# Comm_Interface.net
KiCad netlist of a schematic drawn in Altium Designer
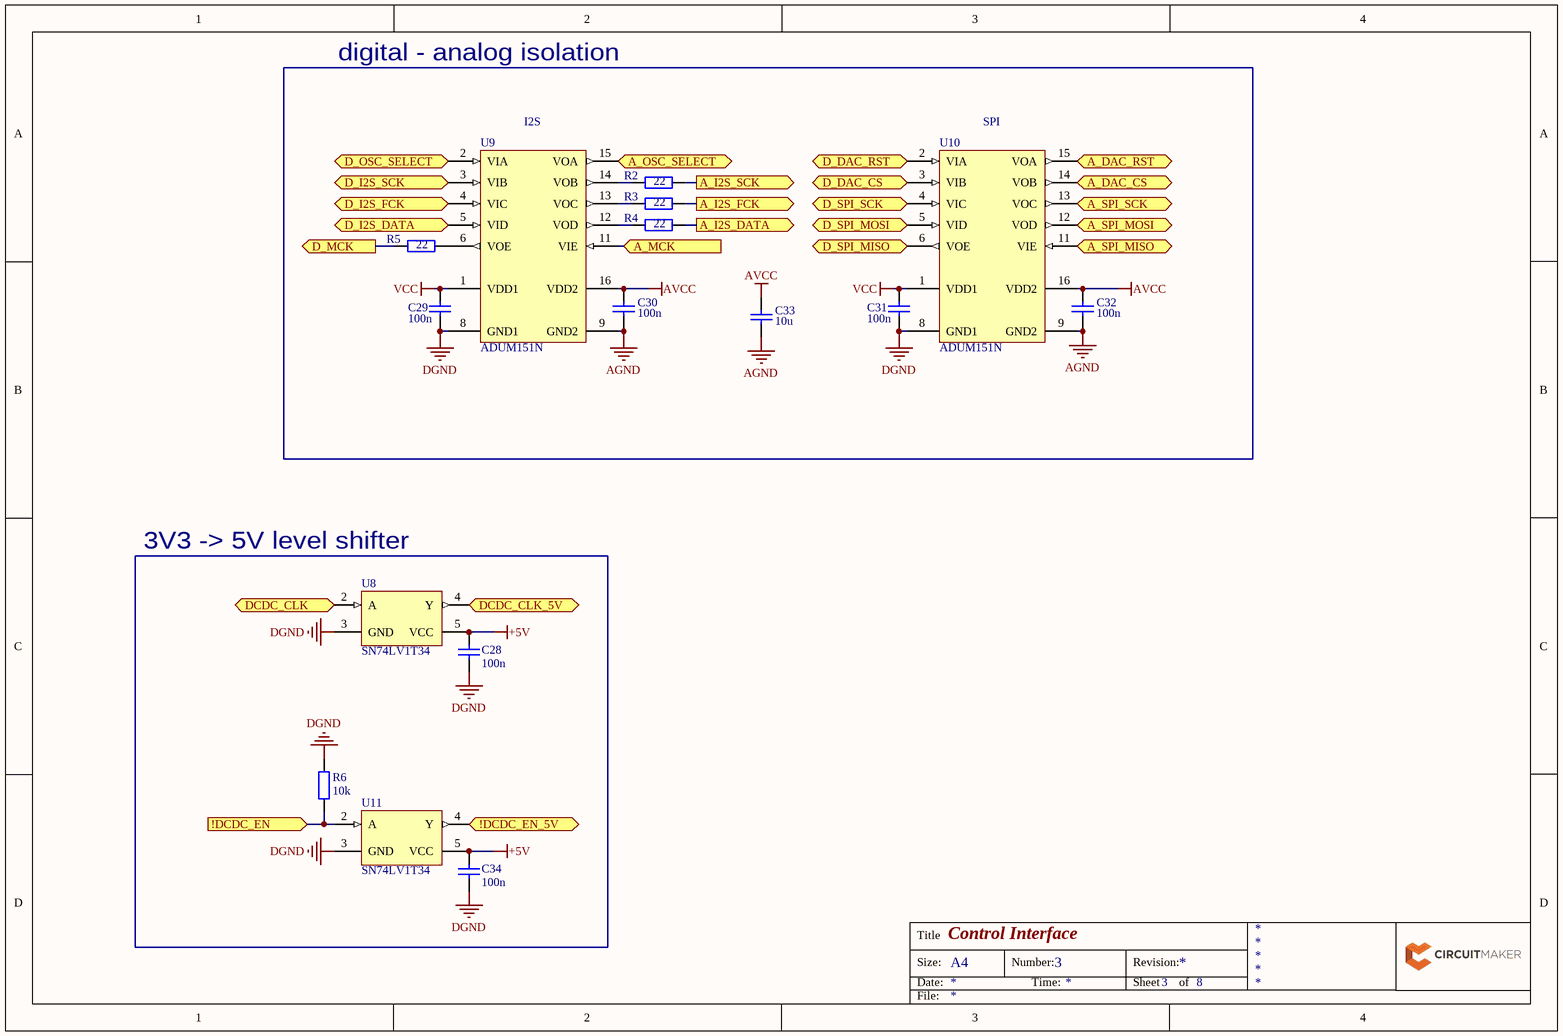
[diagram p0: Comm_Interface.SchDoc]

(export (version "E")
  (design (tool "Eeschema 10.0.6"))
  (components
    (comp (ref "C28")
      (value "100n")
      (footprint "PCB-rf0pzaa82dpbeu9l4sxm-1")
      (description "Capacitor 0603")
      (fields (field (name "LCSC PART #") "C14663") (field (name "LCSC PART #_1") "C109474"))
      (libsource (lib "FavoritesLibrary") (part "SYM-x8hddryxw4o380xfi98v-1"))
    )
    (comp (ref "C29")
      (value "100n")
      (footprint "PCB-rf0pzaa82dpbeu9l4sxm-1")
      (description "Capacitor 0603")
      (fields (field (name "LCSC PART #") "C14663") (field (name "LCSC PART #_1") "C109474"))
      (libsource (lib "FavoritesLibrary") (part "SYM-x8hddryxw4o380xfi98v-1"))
    )
    (comp (ref "C30")
      (value "100n")
      (footprint "PCB-rf0pzaa82dpbeu9l4sxm-1")
      (description "Capacitor 0603")
      (fields (field (name "LCSC PART #") "C14663") (field (name "LCSC PART #_1") "C109474"))
      (libsource (lib "FavoritesLibrary") (part "SYM-x8hddryxw4o380xfi98v-1"))
    )
    (comp (ref "C31")
      (value "100n")
      (footprint "PCB-rf0pzaa82dpbeu9l4sxm-1")
      (description "Capacitor 0603")
      (fields (field (name "LCSC PART #") "C14663") (field (name "LCSC PART #_1") "C109474"))
      (libsource (lib "FavoritesLibrary") (part "SYM-x8hddryxw4o380xfi98v-1"))
    )
    (comp (ref "C32")
      (value "100n")
      (footprint "PCB-rf0pzaa82dpbeu9l4sxm-1")
      (description "Capacitor 0603")
      (fields (field (name "LCSC PART #") "C14663") (field (name "LCSC PART #_1") "C109474"))
      (libsource (lib "FavoritesLibrary") (part "SYM-x8hddryxw4o380xfi98v-1"))
    )
    (comp (ref "C33")
      (value "10u")
      (footprint "PCB-rf0pzaa82dpbeu9l4sxm-1")
      (description "Capacitor 0603")
      (fields (field (name "LCSC PART #") "C19702"))
      (libsource (lib "FavoritesLibrary") (part "SYM-x8hddryxw4o380xfi98v-1"))
    )
    (comp (ref "C34")
      (value "100n")
      (footprint "PCB-rf0pzaa82dpbeu9l4sxm-1")
      (description "Capacitor 0603")
      (fields (field (name "LCSC PART #") "C14663") (field (name "LCSC PART #_1") "C109474"))
      (libsource (lib "FavoritesLibrary") (part "SYM-x8hddryxw4o380xfi98v-1"))
    )
    (comp (ref "R2")
      (value "22")
      (footprint "PCB-3d5y3t7f8drf35yjcj59-1")
      (description "Resistor 0603")
      (fields (field (name "LCSC PART #") "C23345"))
      (libsource (lib "") (part "SYM-xcu3s4ikiffkkgbeyow5-1_1"))
    )
    (comp (ref "R3")
      (value "22")
      (footprint "PCB-3d5y3t7f8drf35yjcj59-1")
      (description "Resistor 0603")
      (fields (field (name "LCSC PART #") "C23345"))
      (libsource (lib "") (part "SYM-xcu3s4ikiffkkgbeyow5-1_1"))
    )
    (comp (ref "R4")
      (value "22")
      (footprint "PCB-3d5y3t7f8drf35yjcj59-1")
      (description "Resistor 0603")
      (fields (field (name "LCSC PART #") "C23345"))
      (libsource (lib "") (part "SYM-xcu3s4ikiffkkgbeyow5-1_1"))
    )
    (comp (ref "R5")
      (value "22")
      (footprint "PCB-3d5y3t7f8drf35yjcj59-1")
      (description "Resistor 0603")
      (fields (field (name "LCSC PART #") "C23345"))
      (libsource (lib "") (part "SYM-xcu3s4ikiffkkgbeyow5-1_1"))
    )
    (comp (ref "R6")
      (value "10k")
      (footprint "PCB-3d5y3t7f8drf35yjcj59-1")
      (description "Resistor 0603")
      (fields (field (name "LCSC PART #") "C25804") (field (name "LCSC PART #_1") "C19702"))
      (libsource (lib "FavoritesLibrary") (part "SYM-xcu3s4ikiffkkgbeyow5-1"))
    )
    (comp (ref "U8")
      (value "SN74LV1T34")
      (footprint "PCB-0ardthfs7lzl2yengne1-1")
      (description "Single Power Supply BUFFER Logic Level Shifter (no enable) 5-SC70 -40 to 125")
      (fields (field (name "MANUFACTURER PART NUMBER") "SN74LV1T34DCKR"))
      (libsource (lib "CommunityVault") (part "SYM-3a3bf2ca9c96e5fc-1"))
    )
    (comp (ref "U9")
      (value "ADUM151N")
      (footprint "SOP16")
      (description "Digital Isolator CMOS 5-CH 150Mbps 16-Pin SOIC N Tube")
      (libsource (lib "CommunityVault") (part "SYM-8a0e4768d24455c9-1"))
    )
    (comp (ref "U10")
      (value "ADUM151N")
      (footprint "SOP16")
      (description "Digital Isolator CMOS 5-CH 150Mbps 16-Pin SOIC N Tube")
      (libsource (lib "CommunityVault") (part "SYM-8a0e4768d24455c9-1"))
    )
    (comp (ref "U11")
      (value "SN74LV1T34")
      (footprint "PCB-0ardthfs7lzl2yengne1-1")
      (description "Single Power Supply BUFFER Logic Level Shifter (no enable) 5-SC70 -40 to 125")
      (fields (field (name "MANUFACTURER PART NUMBER") "SN74LV1T34DCKR"))
      (libsource (lib "CommunityVault") (part "SYM-3a3bf2ca9c96e5fc-1"))
    )
  )
  (nets
    (net (code "1") (name "+5V") (class "Default")
      (node (ref "C28") (pin "2") (pinfunction "2_2") (pintype "passive"))
      (node (ref "C34") (pin "2") (pinfunction "2_2") (pintype "passive"))
      (node (ref "U11") (pin "5") (pinfunction "VCC_5") (pintype "power_in"))
      (node (ref "U8") (pin "5") (pinfunction "VCC_5") (pintype "power_in"))
    )
    (net (code "2") (name "/!DCDC_EN") (class "Default")
      (node (ref "R6") (pin "1") (pinfunction "1_1") (pintype "passive"))
      (node (ref "U11") (pin "2") (pinfunction "A_2") (pintype "input"))
    )
    (net (code "3") (name "/!DCDC_EN_5V") (class "Default")
      (node (ref "U11") (pin "4") (pinfunction "Y_4") (pintype "output"))
    )
    (net (code "4") (name "/A_DAC_CS") (class "Default")
      (node (ref "U10") (pin "14") (pinfunction "VOB_14") (pintype "output"))
    )
    (net (code "5") (name "/A_DAC_RST") (class "Default")
      (node (ref "U10") (pin "15") (pinfunction "VOA_15") (pintype "output"))
    )
    (net (code "6") (name "/A_I2S_DATA") (class "Default")
      (node (ref "R4") (pin "1") (pinfunction "1_1") (pintype "passive"))
    )
    (net (code "7") (name "/A_I2S_FCK") (class "Default")
      (node (ref "R3") (pin "1") (pinfunction "1_1") (pintype "passive"))
    )
    (net (code "8") (name "/A_I2S_SCK") (class "Default")
      (node (ref "R2") (pin "1") (pinfunction "1_1") (pintype "passive"))
    )
    (net (code "9") (name "/A_MCK") (class "Default")
      (node (ref "U9") (pin "11") (pinfunction "VIE_11") (pintype "input"))
    )
    (net (code "10") (name "/A_OSC_SELECT") (class "Default")
      (node (ref "U9") (pin "15") (pinfunction "VOA_15") (pintype "output"))
    )
    (net (code "11") (name "/A_SPI_MISO") (class "Default")
      (node (ref "U10") (pin "11") (pinfunction "VIE_11") (pintype "input"))
    )
    (net (code "12") (name "/A_SPI_MOSI") (class "Default")
      (node (ref "U10") (pin "12") (pinfunction "VOD_12") (pintype "output"))
    )
    (net (code "13") (name "/A_SPI_SCK") (class "Default")
      (node (ref "U10") (pin "13") (pinfunction "VOC_13") (pintype "output"))
    )
    (net (code "14") (name "/DCDC_CLK") (class "Default")
      (node (ref "U8") (pin "2") (pinfunction "A_2") (pintype "input"))
    )
    (net (code "15") (name "/DCDC_CLK_5V") (class "Default")
      (node (ref "U8") (pin "4") (pinfunction "Y_4") (pintype "output"))
    )
    (net (code "16") (name "/D_DAC_CS") (class "Default")
      (node (ref "U10") (pin "3") (pinfunction "VIB_3") (pintype "input"))
    )
    (net (code "17") (name "/D_DAC_RST") (class "Default")
      (node (ref "U10") (pin "2") (pinfunction "VIA_2") (pintype "input"))
    )
    (net (code "18") (name "/D_I2S_DATA") (class "Default")
      (node (ref "U9") (pin "5") (pinfunction "VID_5") (pintype "input"))
    )
    (net (code "19") (name "/D_I2S_FCK") (class "Default")
      (node (ref "U9") (pin "4") (pinfunction "VIC_4") (pintype "input"))
    )
    (net (code "20") (name "/D_I2S_SCK") (class "Default")
      (node (ref "U9") (pin "3") (pinfunction "VIB_3") (pintype "input"))
    )
    (net (code "21") (name "/D_MCK") (class "Default")
      (node (ref "R5") (pin "2") (pinfunction "2_2") (pintype "passive"))
    )
    (net (code "22") (name "/D_OSC_SELECT") (class "Default")
      (node (ref "U9") (pin "2") (pinfunction "VIA_2") (pintype "input"))
    )
    (net (code "23") (name "/D_SPI_MISO") (class "Default")
      (node (ref "U10") (pin "6") (pinfunction "VOE_6") (pintype "output"))
    )
    (net (code "24") (name "/D_SPI_MOSI") (class "Default")
      (node (ref "U10") (pin "5") (pinfunction "VID_5") (pintype "input"))
    )
    (net (code "25") (name "/D_SPI_SCK") (class "Default")
      (node (ref "U10") (pin "4") (pinfunction "VIC_4") (pintype "input"))
    )
    (net (code "26") (name "AGND") (class "Default")
      (node (ref "C30") (pin "1") (pinfunction "1_1") (pintype "passive"))
      (node (ref "C32") (pin "1") (pinfunction "1_1") (pintype "passive"))
      (node (ref "C33") (pin "1") (pinfunction "1_1") (pintype "passive"))
      (node (ref "U10") (pin "9") (pinfunction "GND2_9") (pintype "power_in"))
      (node (ref "U9") (pin "9") (pinfunction "GND2_9") (pintype "power_in"))
    )
    (net (code "27") (name "AVCC") (class "Default")
      (node (ref "C30") (pin "2") (pinfunction "2_2") (pintype "passive"))
      (node (ref "C32") (pin "2") (pinfunction "2_2") (pintype "passive"))
      (node (ref "C33") (pin "2") (pinfunction "2_2") (pintype "passive"))
      (node (ref "U10") (pin "16") (pinfunction "VDD2_16") (pintype "power_in"))
      (node (ref "U9") (pin "16") (pinfunction "VDD2_16") (pintype "power_in"))
    )
    (net (code "28") (name "DGND") (class "Default")
      (node (ref "C28") (pin "1") (pinfunction "1_1") (pintype "passive"))
      (node (ref "C29") (pin "1") (pinfunction "1_1") (pintype "passive"))
      (node (ref "C31") (pin "1") (pinfunction "1_1") (pintype "passive"))
      (node (ref "C34") (pin "1") (pinfunction "1_1") (pintype "passive"))
      (node (ref "R6") (pin "2") (pinfunction "2_2") (pintype "passive"))
      (node (ref "U10") (pin "8") (pinfunction "GND1_8") (pintype "power_in"))
      (node (ref "U11") (pin "3") (pinfunction "GND_3") (pintype "power_in"))
      (node (ref "U8") (pin "3") (pinfunction "GND_3") (pintype "power_in"))
      (node (ref "U9") (pin "8") (pinfunction "GND1_8") (pintype "power_in"))
    )
    (net (code "29") (name "Net-(U9-VOB)") (class "Default")
      (node (ref "R2") (pin "2") (pinfunction "2_2") (pintype "passive"))
      (node (ref "U9") (pin "14") (pinfunction "VOB_14") (pintype "output"))
    )
    (net (code "30") (name "Net-(U9-VOC)") (class "Default")
      (node (ref "R3") (pin "2") (pinfunction "2_2") (pintype "passive"))
      (node (ref "U9") (pin "13") (pinfunction "VOC_13") (pintype "output"))
    )
    (net (code "31") (name "Net-(U9-VOD)") (class "Default")
      (node (ref "R4") (pin "2") (pinfunction "2_2") (pintype "passive"))
      (node (ref "U9") (pin "12") (pinfunction "VOD_12") (pintype "output"))
    )
    (net (code "32") (name "Net-(U9-VOE)") (class "Default")
      (node (ref "R5") (pin "1") (pinfunction "1_1") (pintype "passive"))
      (node (ref "U9") (pin "6") (pinfunction "VOE_6") (pintype "output"))
    )
    (net (code "33") (name "VCC") (class "Default")
      (node (ref "C29") (pin "2") (pinfunction "2_2") (pintype "passive"))
      (node (ref "C31") (pin "2") (pinfunction "2_2") (pintype "passive"))
      (node (ref "U10") (pin "1") (pinfunction "VDD1_1") (pintype "power_in"))
      (node (ref "U9") (pin "1") (pinfunction "VDD1_1") (pintype "power_in"))
    )
  )
)
